# mini_digitboard.net
KiCad netlist of a schematic drawn in EAGLE
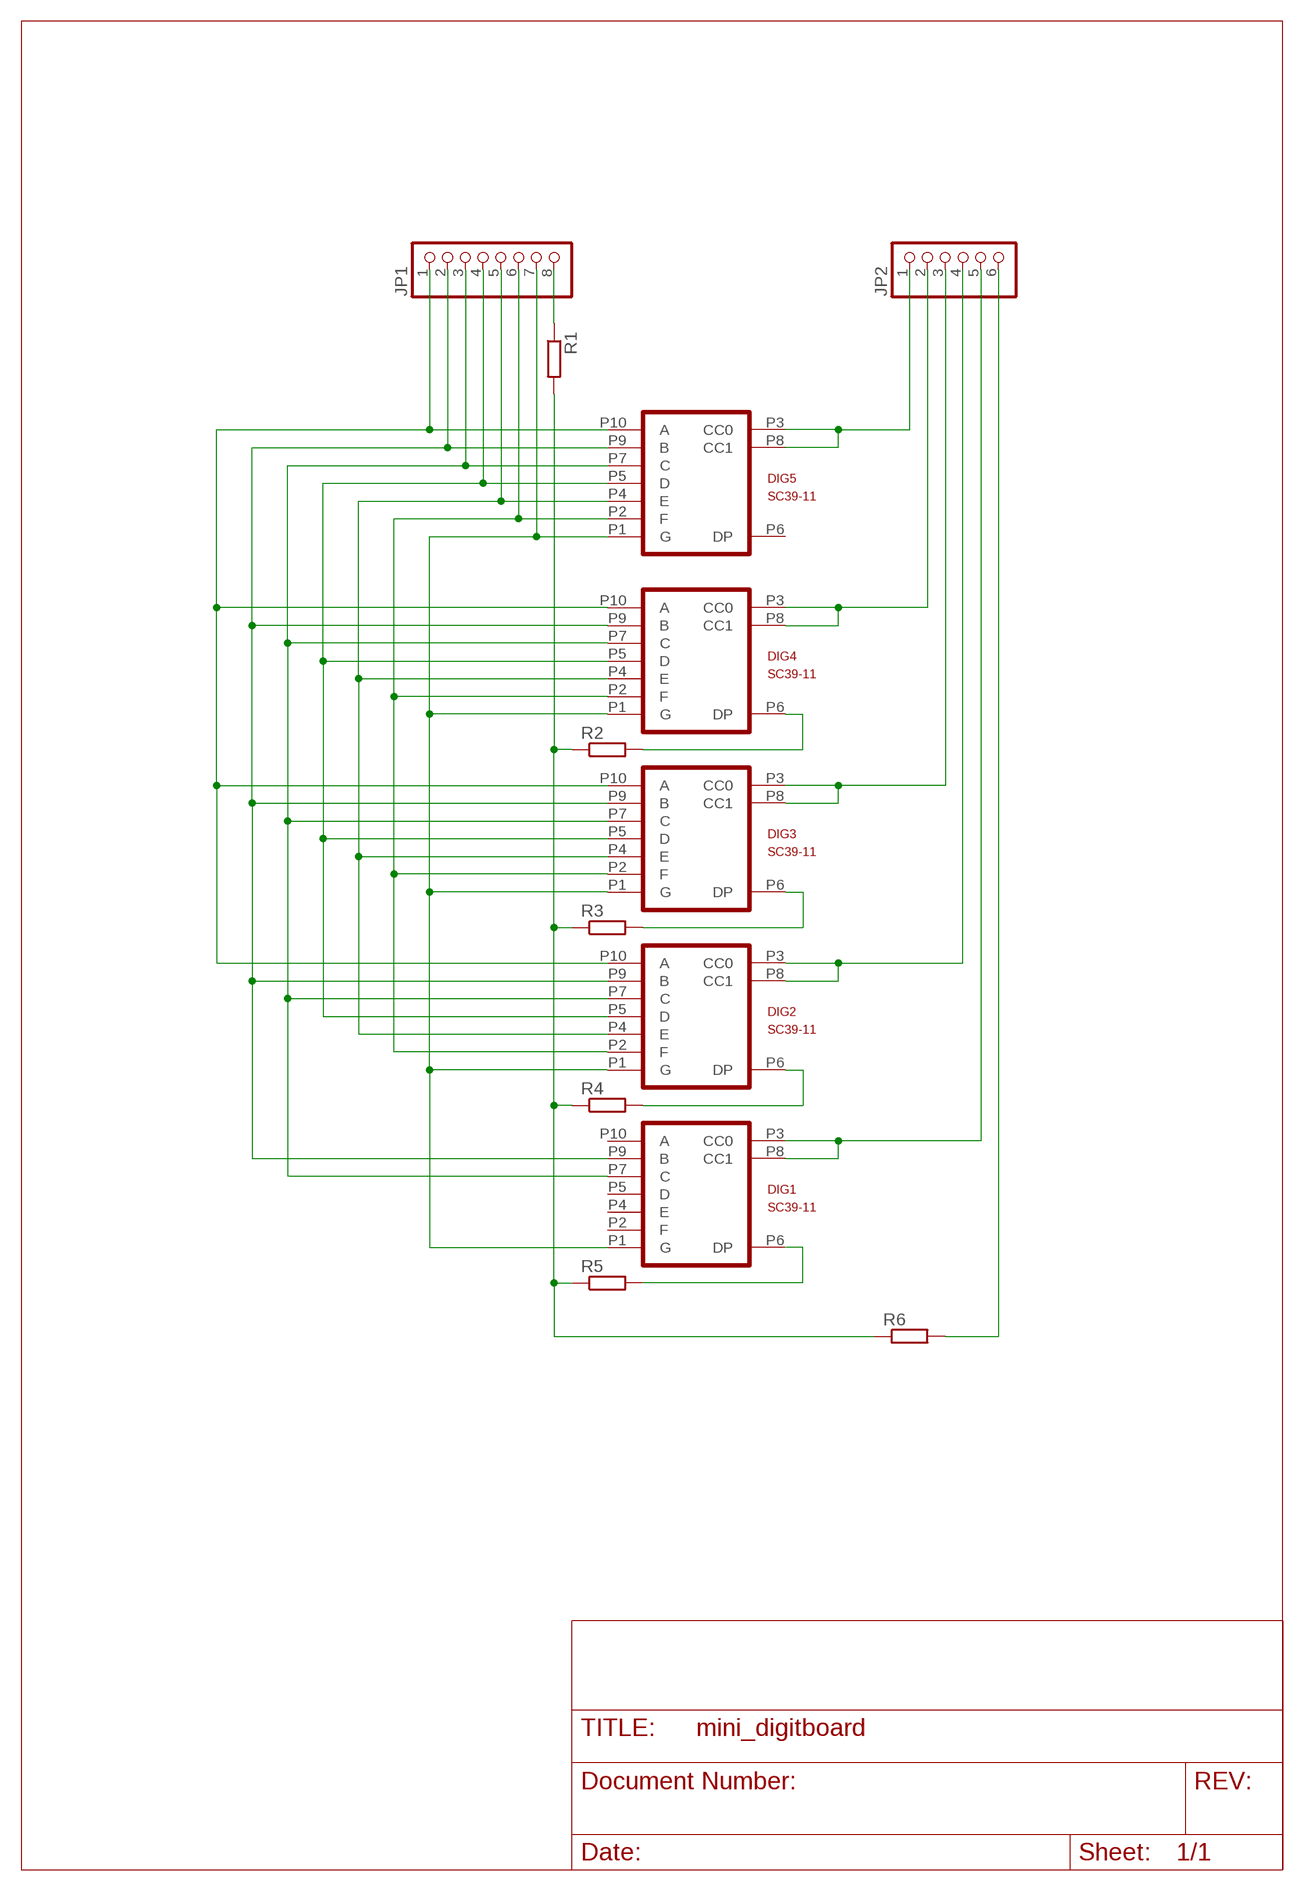
[diagram p0: schematic, sheet 1]

(export (version "E")
  (design (tool "Eeschema 10.0.6"))
  (components
    (comp (ref "DIG1")
      (value "SC39-11")
      (footprint "eagle-import:SC39-11")
      (libsource (lib "eagle-import") (part "SC39-11"))
    )
    (comp (ref "DIG2")
      (value "SC39-11")
      (footprint "eagle-import:SC39-11")
      (libsource (lib "eagle-import") (part "SC39-11"))
    )
    (comp (ref "DIG3")
      (value "SC39-11")
      (footprint "eagle-import:SC39-11")
      (libsource (lib "eagle-import") (part "SC39-11"))
    )
    (comp (ref "DIG4")
      (value "SC39-11")
      (footprint "eagle-import:SC39-11")
      (libsource (lib "eagle-import") (part "SC39-11"))
    )
    (comp (ref "DIG5")
      (value "SC39-11")
      (footprint "eagle-import:SC39-11")
      (libsource (lib "eagle-import") (part "SC39-11"))
    )
    (comp (ref "JP1")
      (value "PINHD-1X8")
      (footprint "eagle-import:1X08")
      (libsource (lib "eagle-import") (part "PINHD-1X8"))
    )
    (comp (ref "JP2")
      (value "PINHD-1X6")
      (footprint "eagle-import:1X06")
      (libsource (lib "eagle-import") (part "PINHD-1X6"))
    )
    (comp (ref "R1")
      (value "R-EU_R0603")
      (footprint "eagle-import:R0603")
      (libsource (lib "eagle-import") (part "R-EU_R0603"))
    )
    (comp (ref "R2")
      (value "R-EU_R0603")
      (footprint "eagle-import:R0603")
      (libsource (lib "eagle-import") (part "R-EU_R0603"))
    )
    (comp (ref "R3")
      (value "R-EU_R0603")
      (footprint "eagle-import:R0603")
      (libsource (lib "eagle-import") (part "R-EU_R0603"))
    )
    (comp (ref "R4")
      (value "R-EU_R0603")
      (footprint "eagle-import:R0603")
      (libsource (lib "eagle-import") (part "R-EU_R0603"))
    )
    (comp (ref "R5")
      (value "R-EU_R0603")
      (footprint "eagle-import:R0603")
      (libsource (lib "eagle-import") (part "R-EU_R0603"))
    )
    (comp (ref "R6")
      (value "R-EU_R0603")
      (footprint "eagle-import:R0603")
      (libsource (lib "eagle-import") (part "R-EU_R0603"))
    )
  )
  (nets
    (net (code "1") (name "Net-(DIG1-B)") (class "Default")
      (node (ref "DIG1") (pin "P9") (pinfunction "B_P9") (pintype "bidirectional"))
      (node (ref "DIG2") (pin "P9") (pinfunction "B_P9") (pintype "bidirectional"))
      (node (ref "DIG3") (pin "P9") (pinfunction "B_P9") (pintype "bidirectional"))
      (node (ref "DIG4") (pin "P9") (pinfunction "B_P9") (pintype "bidirectional"))
      (node (ref "DIG5") (pin "P9") (pinfunction "B_P9") (pintype "bidirectional"))
      (node (ref "JP1") (pin "2") (pinfunction "2_2") (pintype "passive"))
    )
    (net (code "2") (name "Net-(DIG1-C)") (class "Default")
      (node (ref "DIG1") (pin "P7") (pinfunction "C_P7") (pintype "bidirectional"))
      (node (ref "DIG2") (pin "P7") (pinfunction "C_P7") (pintype "bidirectional"))
      (node (ref "DIG3") (pin "P7") (pinfunction "C_P7") (pintype "bidirectional"))
      (node (ref "DIG4") (pin "P7") (pinfunction "C_P7") (pintype "bidirectional"))
      (node (ref "DIG5") (pin "P7") (pinfunction "C_P7") (pintype "bidirectional"))
      (node (ref "JP1") (pin "3") (pinfunction "3_3") (pintype "passive"))
    )
    (net (code "3") (name "Net-(DIG1-CC0)") (class "Default")
      (node (ref "DIG1") (pin "P3") (pinfunction "CC0_P3") (pintype "bidirectional"))
      (node (ref "DIG1") (pin "P8") (pinfunction "CC1_P8") (pintype "bidirectional"))
      (node (ref "JP2") (pin "5") (pinfunction "5_5") (pintype "passive"))
    )
    (net (code "4") (name "Net-(DIG1-DP)") (class "Default")
      (node (ref "DIG1") (pin "P6") (pinfunction "DP_P6") (pintype "bidirectional"))
      (node (ref "R5") (pin "2") (pinfunction "2_2") (pintype "passive"))
    )
    (net (code "5") (name "Net-(DIG1-G)") (class "Default")
      (node (ref "DIG1") (pin "P1") (pinfunction "G_P1") (pintype "bidirectional"))
      (node (ref "DIG2") (pin "P1") (pinfunction "G_P1") (pintype "bidirectional"))
      (node (ref "DIG3") (pin "P1") (pinfunction "G_P1") (pintype "bidirectional"))
      (node (ref "DIG4") (pin "P1") (pinfunction "G_P1") (pintype "bidirectional"))
      (node (ref "DIG5") (pin "P1") (pinfunction "G_P1") (pintype "bidirectional"))
      (node (ref "JP1") (pin "7") (pinfunction "7_7") (pintype "passive"))
    )
    (net (code "6") (name "Net-(DIG2-A)") (class "Default")
      (node (ref "DIG2") (pin "P10") (pinfunction "A_P10") (pintype "bidirectional"))
      (node (ref "DIG3") (pin "P10") (pinfunction "A_P10") (pintype "bidirectional"))
      (node (ref "DIG4") (pin "P10") (pinfunction "A_P10") (pintype "bidirectional"))
      (node (ref "DIG5") (pin "P10") (pinfunction "A_P10") (pintype "bidirectional"))
      (node (ref "JP1") (pin "1") (pinfunction "1_1") (pintype "passive"))
    )
    (net (code "7") (name "Net-(DIG2-CC0)") (class "Default")
      (node (ref "DIG2") (pin "P3") (pinfunction "CC0_P3") (pintype "bidirectional"))
      (node (ref "DIG2") (pin "P8") (pinfunction "CC1_P8") (pintype "bidirectional"))
      (node (ref "JP2") (pin "4") (pinfunction "4_4") (pintype "passive"))
    )
    (net (code "8") (name "Net-(DIG2-D)") (class "Default")
      (node (ref "DIG2") (pin "P5") (pinfunction "D_P5") (pintype "bidirectional"))
      (node (ref "DIG3") (pin "P5") (pinfunction "D_P5") (pintype "bidirectional"))
      (node (ref "DIG4") (pin "P5") (pinfunction "D_P5") (pintype "bidirectional"))
      (node (ref "DIG5") (pin "P5") (pinfunction "D_P5") (pintype "bidirectional"))
      (node (ref "JP1") (pin "4") (pinfunction "4_4") (pintype "passive"))
    )
    (net (code "9") (name "Net-(DIG2-DP)") (class "Default")
      (node (ref "DIG2") (pin "P6") (pinfunction "DP_P6") (pintype "bidirectional"))
      (node (ref "R4") (pin "2") (pinfunction "2_2") (pintype "passive"))
    )
    (net (code "10") (name "Net-(DIG2-E)") (class "Default")
      (node (ref "DIG2") (pin "P4") (pinfunction "E_P4") (pintype "bidirectional"))
      (node (ref "DIG3") (pin "P4") (pinfunction "E_P4") (pintype "bidirectional"))
      (node (ref "DIG4") (pin "P4") (pinfunction "E_P4") (pintype "bidirectional"))
      (node (ref "DIG5") (pin "P4") (pinfunction "E_P4") (pintype "bidirectional"))
      (node (ref "JP1") (pin "5") (pinfunction "5_5") (pintype "passive"))
    )
    (net (code "11") (name "Net-(DIG2-F)") (class "Default")
      (node (ref "DIG2") (pin "P2") (pinfunction "F_P2") (pintype "bidirectional"))
      (node (ref "DIG3") (pin "P2") (pinfunction "F_P2") (pintype "bidirectional"))
      (node (ref "DIG4") (pin "P2") (pinfunction "F_P2") (pintype "bidirectional"))
      (node (ref "DIG5") (pin "P2") (pinfunction "F_P2") (pintype "bidirectional"))
      (node (ref "JP1") (pin "6") (pinfunction "6_6") (pintype "passive"))
    )
    (net (code "12") (name "Net-(DIG3-CC0)") (class "Default")
      (node (ref "DIG3") (pin "P3") (pinfunction "CC0_P3") (pintype "bidirectional"))
      (node (ref "DIG3") (pin "P8") (pinfunction "CC1_P8") (pintype "bidirectional"))
      (node (ref "JP2") (pin "3") (pinfunction "3_3") (pintype "passive"))
    )
    (net (code "13") (name "Net-(DIG3-DP)") (class "Default")
      (node (ref "DIG3") (pin "P6") (pinfunction "DP_P6") (pintype "bidirectional"))
      (node (ref "R3") (pin "2") (pinfunction "2_2") (pintype "passive"))
    )
    (net (code "14") (name "Net-(DIG4-CC0)") (class "Default")
      (node (ref "DIG4") (pin "P3") (pinfunction "CC0_P3") (pintype "bidirectional"))
      (node (ref "DIG4") (pin "P8") (pinfunction "CC1_P8") (pintype "bidirectional"))
      (node (ref "JP2") (pin "2") (pinfunction "2_2") (pintype "passive"))
    )
    (net (code "15") (name "Net-(DIG4-DP)") (class "Default")
      (node (ref "DIG4") (pin "P6") (pinfunction "DP_P6") (pintype "bidirectional"))
      (node (ref "R2") (pin "2") (pinfunction "2_2") (pintype "passive"))
    )
    (net (code "16") (name "Net-(DIG5-CC0)") (class "Default")
      (node (ref "DIG5") (pin "P3") (pinfunction "CC0_P3") (pintype "bidirectional"))
      (node (ref "DIG5") (pin "P8") (pinfunction "CC1_P8") (pintype "bidirectional"))
      (node (ref "JP2") (pin "1") (pinfunction "1_1") (pintype "passive"))
    )
    (net (code "17") (name "Net-(JP1-Pad8)") (class "Default")
      (node (ref "JP1") (pin "8") (pinfunction "8_8") (pintype "passive"))
      (node (ref "R1") (pin "1") (pinfunction "1_1") (pintype "passive"))
    )
    (net (code "18") (name "Net-(JP2-Pad6)") (class "Default")
      (node (ref "JP2") (pin "6") (pinfunction "6_6") (pintype "passive"))
      (node (ref "R6") (pin "2") (pinfunction "2_2") (pintype "passive"))
    )
    (net (code "19") (name "Net-(R1-Pad2)") (class "Default")
      (node (ref "R1") (pin "2") (pinfunction "2_2") (pintype "passive"))
      (node (ref "R2") (pin "1") (pinfunction "1_1") (pintype "passive"))
      (node (ref "R3") (pin "1") (pinfunction "1_1") (pintype "passive"))
      (node (ref "R4") (pin "1") (pinfunction "1_1") (pintype "passive"))
      (node (ref "R5") (pin "1") (pinfunction "1_1") (pintype "passive"))
      (node (ref "R6") (pin "1") (pinfunction "1_1") (pintype "passive"))
    )
    (net (code "20") (name "unconnected-(DIG1-A-PadP10)") (class "Default")
      (node (ref "DIG1") (pin "P10") (pinfunction "A_P10") (pintype "bidirectional"))
    )
    (net (code "21") (name "unconnected-(DIG1-D-PadP5)") (class "Default")
      (node (ref "DIG1") (pin "P5") (pinfunction "D_P5") (pintype "bidirectional"))
    )
    (net (code "22") (name "unconnected-(DIG1-E-PadP4)") (class "Default")
      (node (ref "DIG1") (pin "P4") (pinfunction "E_P4") (pintype "bidirectional"))
    )
    (net (code "23") (name "unconnected-(DIG1-F-PadP2)") (class "Default")
      (node (ref "DIG1") (pin "P2") (pinfunction "F_P2") (pintype "bidirectional"))
    )
    (net (code "24") (name "unconnected-(DIG5-DP-PadP6)") (class "Default")
      (node (ref "DIG5") (pin "P6") (pinfunction "DP_P6") (pintype "bidirectional"))
    )
  )
)
